# JDM2_2-Voltage_JmpConf_VDDctrl.net
KiCad netlist of a schematic drawn in EAGLE
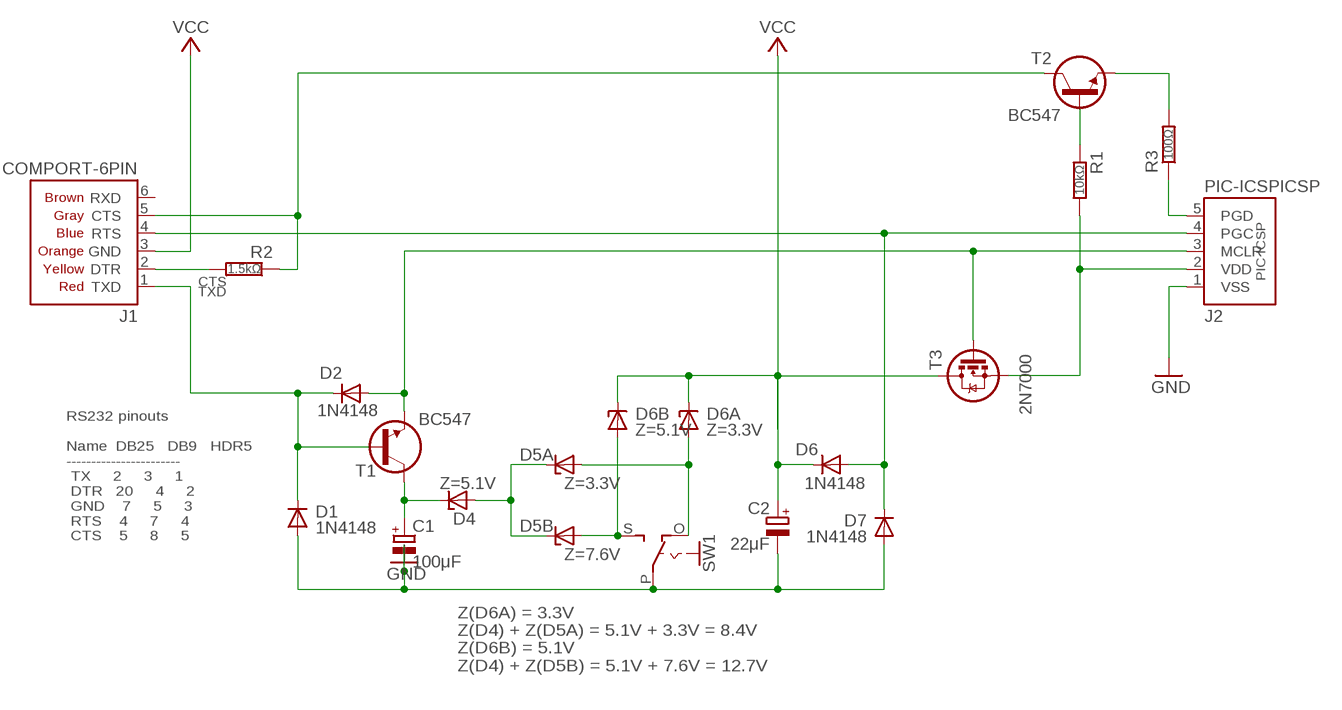
[diagram p0: schematic, sheet 1]

(export (version "E")
  (design (tool "Eeschema 10.0.6"))
  (components
    (comp (ref "C1")
      (value "100μF")
      (footprint "eagle-import:E2,5-5_V")
      (libsource (lib "eagle-import") (part "CPOLE2,5-5/V"))
    )
    (comp (ref "C2")
      (value "22μF")
      (footprint "eagle-import:E2.5-4_V")
      (libsource (lib "eagle-import") (part "CPOLE2,5-4/V"))
    )
    (comp (ref "D1")
      (value "1N4148")
      (footprint "eagle-import:DO34-5")
      (libsource (lib "eagle-import") (part "1N414834-5"))
    )
    (comp (ref "D2")
      (value "1N4148")
      (footprint "eagle-import:DO34-5")
      (libsource (lib "eagle-import") (part "1N414834-5"))
    )
    (comp (ref "D4")
      (value "Z=5.1V")
      (footprint "eagle-import:DO34Z7")
      (libsource (lib "eagle-import") (part "Z-DIODE34Z7"))
    )
    (comp (ref "D5A")
      (value "Z=3.3V")
      (footprint "eagle-import:DO34Z7")
      (libsource (lib "eagle-import") (part "Z-DIODE34Z7"))
    )
    (comp (ref "D5B")
      (value "Z=7.6V")
      (footprint "eagle-import:DO34Z7")
      (libsource (lib "eagle-import") (part "Z-DIODE34Z7"))
    )
    (comp (ref "D6")
      (value "1N4148")
      (footprint "eagle-import:DO34-10V")
      (libsource (lib "eagle-import") (part "1N414834-10V"))
    )
    (comp (ref "D6A")
      (value "Z=3.3V")
      (footprint "eagle-import:DO34Z7V")
      (libsource (lib "eagle-import") (part "Z-DIODE34Z7V"))
    )
    (comp (ref "D6B")
      (value "Z=5.1V")
      (footprint "eagle-import:DO34Z7V")
      (libsource (lib "eagle-import") (part "Z-DIODE34Z7V"))
    )
    (comp (ref "D7")
      (value "1N4148")
      (footprint "eagle-import:DO34-7V")
      (libsource (lib "eagle-import") (part "1N414834-7V"))
    )
    (comp (ref "J1")
      (value "COMPORT-6PIN")
      (footprint "eagle-import:RS232-6PIN")
      (libsource (lib "eagle-import") (part "COMPORT-6PIN"))
    )
    (comp (ref "J2")
      (value "PIC-ICSPICSP")
      (footprint "eagle-import:PIC-ICSP")
      (libsource (lib "eagle-import") (part "PIC-ICSPICSP"))
    )
    (comp (ref "R1")
      (value "10kΩ")
      (footprint "eagle-import:0202_7-V")
      (libsource (lib "eagle-import") (part "R0202/7-V"))
    )
    (comp (ref "R2")
      (value "1.5kΩ")
      (footprint "eagle-import:0202_7-V")
      (libsource (lib "eagle-import") (part "R0202/7-V"))
    )
    (comp (ref "R3")
      (value "100Ω")
      (footprint "eagle-import:0202_7")
      (libsource (lib "eagle-import") (part "R0202/7"))
    )
    (comp (ref "SW1")
      (value "SL-SW-1P-2T-JPSW")
      (footprint "eagle-import:JPSW-1P2T")
      (libsource (lib "eagle-import") (part "SL-SW-1P-2T-JPSW"))
    )
    (comp (ref "T1")
      (value "BC547")
      (footprint "eagle-import:TO92-CBE")
      (libsource (lib "eagle-import") (part "BC547CBE"))
    )
    (comp (ref "T2")
      (value "BC547")
      (footprint "eagle-import:TO92-CBE")
      (libsource (lib "eagle-import") (part "BC547CBE"))
    )
    (comp (ref "T3")
      (value "2N7000")
      (footprint "eagle-import:TO92")
      (libsource (lib "eagle-import") (part "2N7000"))
    )
  )
  (nets
    (net (code "1") (name "/CTS") (class "Default")
      (node (ref "J1") (pin "5") (pinfunction "CTS_5") (pintype "passive"))
      (node (ref "R2") (pin "1") (pinfunction "1_1") (pintype "passive"))
      (node (ref "T2") (pin "C") (pinfunction "C_C") (pintype "passive"))
    )
    (net (code "2") (name "/TXD") (class "Default")
      (node (ref "D1") (pin "C") (pinfunction "C_C") (pintype "passive"))
      (node (ref "D2") (pin "C") (pinfunction "C_C") (pintype "passive"))
      (node (ref "J1") (pin "1") (pinfunction "TXD_1") (pintype "passive"))
      (node (ref "T1") (pin "B") (pinfunction "B_B") (pintype "passive"))
    )
    (net (code "3") (name "GND") (class "Default")
      (node (ref "C1") (pin "-") (pinfunction "-_-") (pintype "passive"))
      (node (ref "C2") (pin "-") (pinfunction "-_-") (pintype "passive"))
      (node (ref "D1") (pin "A") (pinfunction "A_A") (pintype "passive"))
      (node (ref "D7") (pin "A") (pinfunction "A_A") (pintype "passive"))
      (node (ref "J2") (pin "1") (pinfunction "VSS_1") (pintype "passive"))
      (node (ref "SW1") (pin "P") (pinfunction "P_P") (pintype "passive"))
    )
    (net (code "4") (name "Net-(C1-Pad+)") (class "Default")
      (node (ref "C1") (pin "+") (pinfunction "+_+") (pintype "passive"))
      (node (ref "D4") (pin "C") (pinfunction "C_C") (pintype "passive"))
      (node (ref "T1") (pin "C") (pinfunction "C_C") (pintype "passive"))
    )
    (net (code "5") (name "Net-(D4-PadA)") (class "Default")
      (node (ref "D4") (pin "A") (pinfunction "A_A") (pintype "passive"))
      (node (ref "D5A") (pin "C") (pinfunction "C_C") (pintype "passive"))
      (node (ref "D5B") (pin "C") (pinfunction "C_C") (pintype "passive"))
    )
    (net (code "6") (name "Net-(D5A-PadA)") (class "Default")
      (node (ref "D5A") (pin "A") (pinfunction "A_A") (pintype "passive"))
      (node (ref "D6A") (pin "A") (pinfunction "A_A") (pintype "passive"))
      (node (ref "SW1") (pin "O") (pinfunction "O_O") (pintype "passive"))
    )
    (net (code "7") (name "Net-(D5B-PadA)") (class "Default")
      (node (ref "D5B") (pin "A") (pinfunction "A_A") (pintype "passive"))
      (node (ref "D6B") (pin "A") (pinfunction "A_A") (pintype "passive"))
      (node (ref "SW1") (pin "S") (pinfunction "S_S") (pintype "passive"))
    )
    (net (code "8") (name "Net-(J1-DTR)") (class "Default")
      (node (ref "J1") (pin "2") (pinfunction "DTR_2") (pintype "passive"))
      (node (ref "R2") (pin "2") (pinfunction "2_2") (pintype "passive"))
    )
    (net (code "9") (name "Net-(J1-RTS)") (class "Default")
      (node (ref "D6") (pin "A") (pinfunction "A_A") (pintype "passive"))
      (node (ref "D7") (pin "C") (pinfunction "C_C") (pintype "passive"))
      (node (ref "J1") (pin "4") (pinfunction "RTS_4") (pintype "passive"))
      (node (ref "J2") (pin "4") (pinfunction "PGC_4") (pintype "passive"))
    )
    (net (code "10") (name "Net-(J2-MCLR)") (class "Default")
      (node (ref "D2") (pin "A") (pinfunction "A_A") (pintype "passive"))
      (node (ref "J2") (pin "3") (pinfunction "MCLR_3") (pintype "passive"))
      (node (ref "T1") (pin "E") (pinfunction "E_E") (pintype "passive"))
      (node (ref "T3") (pin "2") (pinfunction "G_2") (pintype "passive"))
    )
    (net (code "11") (name "Net-(J2-PGD)") (class "Default")
      (node (ref "J2") (pin "5") (pinfunction "PGD_5") (pintype "passive"))
      (node (ref "R3") (pin "1") (pinfunction "1_1") (pintype "passive"))
    )
    (net (code "12") (name "Net-(J2-VDD)") (class "Default")
      (node (ref "J2") (pin "2") (pinfunction "VDD_2") (pintype "passive"))
      (node (ref "R1") (pin "2") (pinfunction "2_2") (pintype "passive"))
      (node (ref "T3") (pin "1") (pinfunction "S_1") (pintype "passive"))
    )
    (net (code "13") (name "Net-(R1-Pad1)") (class "Default")
      (node (ref "R1") (pin "1") (pinfunction "1_1") (pintype "passive"))
      (node (ref "T2") (pin "B") (pinfunction "B_B") (pintype "passive"))
    )
    (net (code "14") (name "Net-(R3-Pad2)") (class "Default")
      (node (ref "R3") (pin "2") (pinfunction "2_2") (pintype "passive"))
      (node (ref "T2") (pin "E") (pinfunction "E_E") (pintype "passive"))
    )
    (net (code "15") (name "VCC") (class "Default")
      (node (ref "C2") (pin "+") (pinfunction "+_+") (pintype "passive"))
      (node (ref "D6") (pin "C") (pinfunction "C_C") (pintype "passive"))
      (node (ref "D6A") (pin "C") (pinfunction "C_C") (pintype "passive"))
      (node (ref "D6B") (pin "C") (pinfunction "C_C") (pintype "passive"))
      (node (ref "J1") (pin "3") (pinfunction "GND_3") (pintype "passive"))
      (node (ref "T3") (pin "3") (pinfunction "D_3") (pintype "passive"))
    )
    (net (code "16") (name "unconnected-(J1-RXD-Pad6)") (class "Default")
      (node (ref "J1") (pin "6") (pinfunction "RXD_6") (pintype "passive"))
    )
  )
)
